# OperantFEDv8.net
KiCad netlist of a schematic drawn in EAGLE
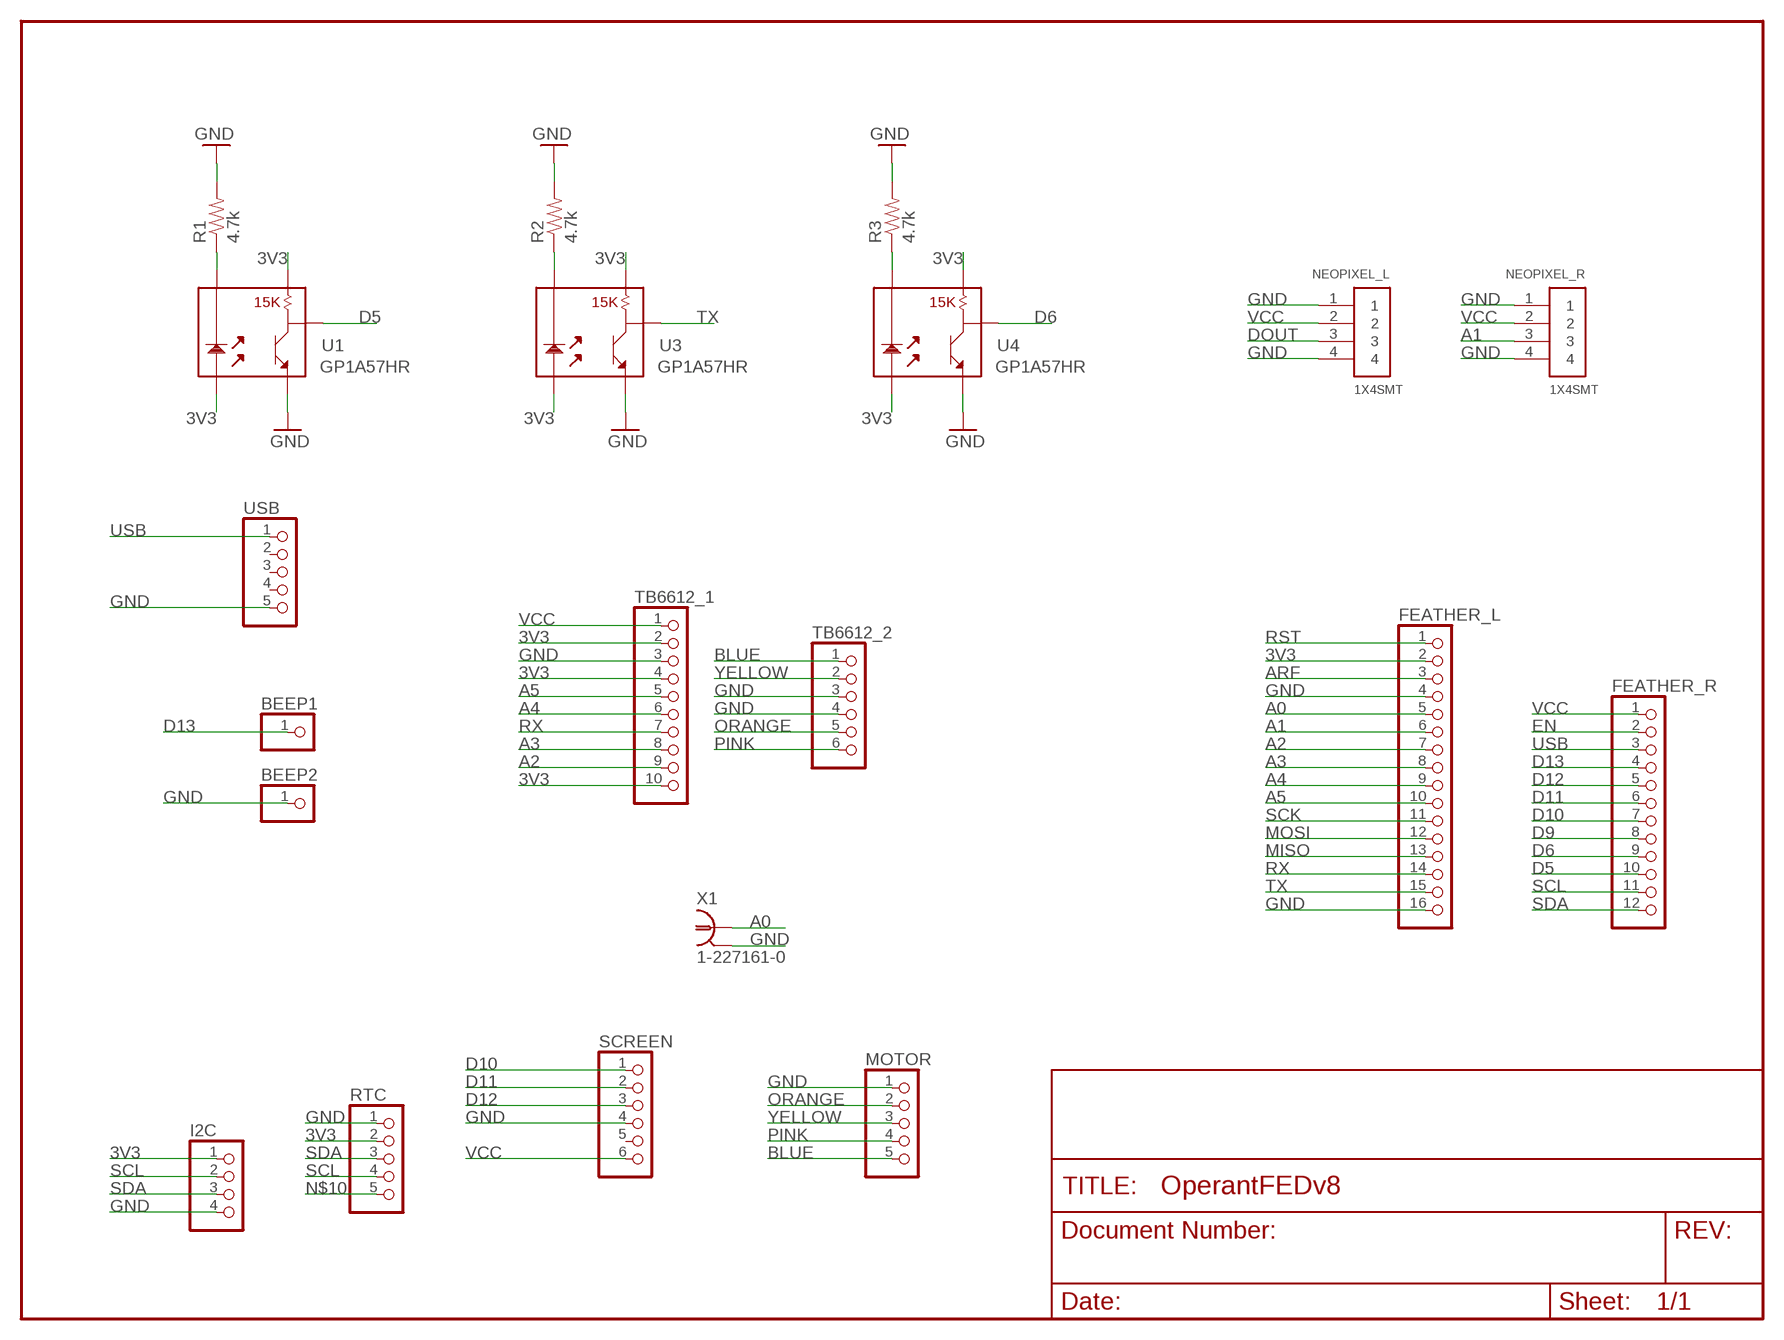
[diagram p0: schematic, sheet 1]

(export (version "E")
  (design (tool "Eeschema 10.0.6"))
  (components
    (comp (ref "BEEP1")
      (value "PINHD-1X1")
      (footprint "eagle-import:1X01")
      (libsource (lib "eagle-import") (part "PINHD-1X1"))
    )
    (comp (ref "BEEP2")
      (value "PINHD-1X1")
      (footprint "eagle-import:1X01")
      (libsource (lib "eagle-import") (part "PINHD-1X1"))
    )
    (comp (ref "FEATHER_L")
      (value "PINHD-1X16")
      (footprint "eagle-import:1X16")
      (libsource (lib "eagle-import") (part "PINHD-1X16"))
    )
    (comp (ref "FEATHER_R")
      (value "PINHD-1X12")
      (footprint "eagle-import:1X12")
      (libsource (lib "eagle-import") (part "PINHD-1X12"))
    )
    (comp (ref "I2C")
      (value "PINHD-1X4")
      (footprint "eagle-import:1X04")
      (libsource (lib "eagle-import") (part "PINHD-1X4"))
    )
    (comp (ref "MOTOR")
      (value "PINHD-1X5")
      (footprint "eagle-import:1X05")
      (libsource (lib "eagle-import") (part "PINHD-1X5"))
    )
    (comp (ref "NEOPIXEL_L")
      (value "1X4SMT")
      (footprint "eagle-import:1X4-SMT")
      (libsource (lib "eagle-import") (part "1X4SMT"))
    )
    (comp (ref "NEOPIXEL_R")
      (value "1X4SMT")
      (footprint "eagle-import:1X4-SMT")
      (libsource (lib "eagle-import") (part "1X4SMT"))
    )
    (comp (ref "R1")
      (value "4.7k")
      (footprint "eagle-import:AXIAL-0.3")
      (libsource (lib "eagle-import") (part "RESISTORPTH1"))
    )
    (comp (ref "R2")
      (value "4.7k")
      (footprint "eagle-import:AXIAL-0.3")
      (libsource (lib "eagle-import") (part "RESISTORPTH1"))
    )
    (comp (ref "R3")
      (value "4.7k")
      (footprint "eagle-import:AXIAL-0.3")
      (libsource (lib "eagle-import") (part "RESISTORPTH1"))
    )
    (comp (ref "RTC")
      (value "PINHD-1X5")
      (footprint "eagle-import:1X05")
      (libsource (lib "eagle-import") (part "PINHD-1X5"))
    )
    (comp (ref "SCREEN")
      (value "PINHD-1X6")
      (footprint "eagle-import:1X06")
      (libsource (lib "eagle-import") (part "PINHD-1X6"))
    )
    (comp (ref "TB6612_1")
      (value "PINHD-1X10")
      (footprint "eagle-import:1X10")
      (libsource (lib "eagle-import") (part "PINHD-1X10"))
    )
    (comp (ref "TB6612_2")
      (value "PINHD-1X6")
      (footprint "eagle-import:1X06")
      (libsource (lib "eagle-import") (part "PINHD-1X6"))
    )
    (comp (ref "U1")
      (value "GP1A57HR")
      (footprint "eagle-import:GP1A57HR")
      (libsource (lib "eagle-import") (part "GP1A57HR"))
    )
    (comp (ref "U3")
      (value "GP1A57HR")
      (footprint "eagle-import:GP1A57HR")
      (libsource (lib "eagle-import") (part "GP1A57HR"))
    )
    (comp (ref "U4")
      (value "GP1A57HR")
      (footprint "eagle-import:GP1A57HR")
      (libsource (lib "eagle-import") (part "GP1A57HR"))
    )
    (comp (ref "USB")
      (value "PINHD-1X5")
      (footprint "eagle-import:1X05")
      (libsource (lib "eagle-import") (part "PINHD-1X5"))
    )
    (comp (ref "X1")
      (value "1-227161-0")
      (footprint "eagle-import:AMP_227161")
      (fields (field (name "MF") "TYCO ELECTRONICS") (field (name "MPN") "1-227161"))
      (libsource (lib "eagle-import") (part "?2271611--0"))
    )
  )
  (nets
    (net (code "1") (name "/3V3") (class "Default")
      (node (ref "FEATHER_L") (pin "2") (pinfunction "2_2") (pintype "passive"))
      (node (ref "I2C") (pin "1") (pinfunction "1_1") (pintype "passive"))
      (node (ref "RTC") (pin "2") (pinfunction "2_2") (pintype "passive"))
      (node (ref "TB6612_1") (pin "10") (pinfunction "10_10") (pintype "passive"))
      (node (ref "TB6612_1") (pin "2") (pinfunction "2_2") (pintype "passive"))
      (node (ref "TB6612_1") (pin "4") (pinfunction "4_4") (pintype "passive"))
      (node (ref "U1") (pin "1") (pinfunction "1_1") (pintype "bidirectional"))
      (node (ref "U1") (pin "3") (pinfunction "3_3") (pintype "bidirectional"))
      (node (ref "U3") (pin "1") (pinfunction "1_1") (pintype "bidirectional"))
      (node (ref "U3") (pin "3") (pinfunction "3_3") (pintype "bidirectional"))
      (node (ref "U4") (pin "1") (pinfunction "1_1") (pintype "bidirectional"))
      (node (ref "U4") (pin "3") (pinfunction "3_3") (pintype "bidirectional"))
    )
    (net (code "2") (name "/A0") (class "Default")
      (node (ref "FEATHER_L") (pin "5") (pinfunction "5_5") (pintype "passive"))
      (node (ref "X1") (pin "1") (pinfunction "1_1") (pintype "passive"))
    )
    (net (code "3") (name "/A1") (class "Default")
      (node (ref "FEATHER_L") (pin "6") (pinfunction "6_6") (pintype "passive"))
      (node (ref "NEOPIXEL_R") (pin "3") (pinfunction "3_3") (pintype "bidirectional"))
    )
    (net (code "4") (name "/A2") (class "Default")
      (node (ref "FEATHER_L") (pin "7") (pinfunction "7_7") (pintype "passive"))
      (node (ref "TB6612_1") (pin "9") (pinfunction "9_9") (pintype "passive"))
    )
    (net (code "5") (name "/A3") (class "Default")
      (node (ref "FEATHER_L") (pin "8") (pinfunction "8_8") (pintype "passive"))
      (node (ref "TB6612_1") (pin "8") (pinfunction "8_8") (pintype "passive"))
    )
    (net (code "6") (name "/A4") (class "Default")
      (node (ref "FEATHER_L") (pin "9") (pinfunction "9_9") (pintype "passive"))
      (node (ref "TB6612_1") (pin "6") (pinfunction "6_6") (pintype "passive"))
    )
    (net (code "7") (name "/A5") (class "Default")
      (node (ref "FEATHER_L") (pin "10") (pinfunction "10_10") (pintype "passive"))
      (node (ref "TB6612_1") (pin "5") (pinfunction "5_5") (pintype "passive"))
    )
    (net (code "8") (name "/ARF") (class "Default")
      (node (ref "FEATHER_L") (pin "3") (pinfunction "3_3") (pintype "passive"))
    )
    (net (code "9") (name "/BLUE") (class "Default")
      (node (ref "MOTOR") (pin "5") (pinfunction "5_5") (pintype "passive"))
      (node (ref "TB6612_2") (pin "1") (pinfunction "1_1") (pintype "passive"))
    )
    (net (code "10") (name "/D5") (class "Default")
      (node (ref "FEATHER_R") (pin "10") (pinfunction "10_10") (pintype "passive"))
      (node (ref "U1") (pin "4") (pinfunction "4_4") (pintype "bidirectional"))
    )
    (net (code "11") (name "/D6") (class "Default")
      (node (ref "FEATHER_R") (pin "9") (pinfunction "9_9") (pintype "passive"))
      (node (ref "U4") (pin "4") (pinfunction "4_4") (pintype "bidirectional"))
    )
    (net (code "12") (name "/D9") (class "Default")
      (node (ref "FEATHER_R") (pin "8") (pinfunction "8_8") (pintype "passive"))
    )
    (net (code "13") (name "/D10") (class "Default")
      (node (ref "FEATHER_R") (pin "7") (pinfunction "7_7") (pintype "passive"))
      (node (ref "SCREEN") (pin "1") (pinfunction "1_1") (pintype "passive"))
    )
    (net (code "14") (name "/D11") (class "Default")
      (node (ref "FEATHER_R") (pin "6") (pinfunction "6_6") (pintype "passive"))
      (node (ref "SCREEN") (pin "2") (pinfunction "2_2") (pintype "passive"))
    )
    (net (code "15") (name "/D12") (class "Default")
      (node (ref "FEATHER_R") (pin "5") (pinfunction "5_5") (pintype "passive"))
      (node (ref "SCREEN") (pin "3") (pinfunction "3_3") (pintype "passive"))
    )
    (net (code "16") (name "/D13") (class "Default")
      (node (ref "BEEP1") (pin "1") (pinfunction "1_1") (pintype "passive"))
      (node (ref "FEATHER_R") (pin "4") (pinfunction "4_4") (pintype "passive"))
    )
    (net (code "17") (name "/DOUT") (class "Default")
      (node (ref "NEOPIXEL_L") (pin "3") (pinfunction "3_3") (pintype "bidirectional"))
    )
    (net (code "18") (name "/EN") (class "Default")
      (node (ref "FEATHER_R") (pin "2") (pinfunction "2_2") (pintype "passive"))
    )
    (net (code "19") (name "/MISO") (class "Default")
      (node (ref "FEATHER_L") (pin "13") (pinfunction "13_13") (pintype "passive"))
    )
    (net (code "20") (name "/MOSI") (class "Default")
      (node (ref "FEATHER_L") (pin "12") (pinfunction "12_12") (pintype "passive"))
    )
    (net (code "21") (name "/N$10") (class "Default")
      (node (ref "RTC") (pin "5") (pinfunction "5_5") (pintype "passive"))
    )
    (net (code "22") (name "/ORANGE") (class "Default")
      (node (ref "MOTOR") (pin "2") (pinfunction "2_2") (pintype "passive"))
      (node (ref "TB6612_2") (pin "5") (pinfunction "5_5") (pintype "passive"))
    )
    (net (code "23") (name "/PINK") (class "Default")
      (node (ref "MOTOR") (pin "4") (pinfunction "4_4") (pintype "passive"))
      (node (ref "TB6612_2") (pin "6") (pinfunction "6_6") (pintype "passive"))
    )
    (net (code "24") (name "/RST") (class "Default")
      (node (ref "FEATHER_L") (pin "1") (pinfunction "1_1") (pintype "passive"))
    )
    (net (code "25") (name "/RX") (class "Default")
      (node (ref "FEATHER_L") (pin "14") (pinfunction "14_14") (pintype "passive"))
      (node (ref "TB6612_1") (pin "7") (pinfunction "7_7") (pintype "passive"))
    )
    (net (code "26") (name "/SCK") (class "Default")
      (node (ref "FEATHER_L") (pin "11") (pinfunction "11_11") (pintype "passive"))
    )
    (net (code "27") (name "/SCL") (class "Default")
      (node (ref "FEATHER_R") (pin "11") (pinfunction "11_11") (pintype "passive"))
      (node (ref "I2C") (pin "2") (pinfunction "2_2") (pintype "passive"))
      (node (ref "RTC") (pin "4") (pinfunction "4_4") (pintype "passive"))
    )
    (net (code "28") (name "/SDA") (class "Default")
      (node (ref "FEATHER_R") (pin "12") (pinfunction "12_12") (pintype "passive"))
      (node (ref "I2C") (pin "3") (pinfunction "3_3") (pintype "passive"))
      (node (ref "RTC") (pin "3") (pinfunction "3_3") (pintype "passive"))
    )
    (net (code "29") (name "/TX") (class "Default")
      (node (ref "FEATHER_L") (pin "15") (pinfunction "15_15") (pintype "passive"))
      (node (ref "U3") (pin "4") (pinfunction "4_4") (pintype "bidirectional"))
    )
    (net (code "30") (name "/USB") (class "Default")
      (node (ref "FEATHER_R") (pin "3") (pinfunction "3_3") (pintype "passive"))
      (node (ref "USB") (pin "1") (pinfunction "1_1") (pintype "passive"))
    )
    (net (code "31") (name "/VCC") (class "Default")
      (node (ref "FEATHER_R") (pin "1") (pinfunction "1_1") (pintype "passive"))
      (node (ref "NEOPIXEL_L") (pin "2") (pinfunction "2_2") (pintype "bidirectional"))
      (node (ref "NEOPIXEL_R") (pin "2") (pinfunction "2_2") (pintype "bidirectional"))
      (node (ref "SCREEN") (pin "6") (pinfunction "6_6") (pintype "passive"))
      (node (ref "TB6612_1") (pin "1") (pinfunction "1_1") (pintype "passive"))
    )
    (net (code "32") (name "/YELLOW") (class "Default")
      (node (ref "MOTOR") (pin "3") (pinfunction "3_3") (pintype "passive"))
      (node (ref "TB6612_2") (pin "2") (pinfunction "2_2") (pintype "passive"))
    )
    (net (code "33") (name "GND") (class "Default")
      (node (ref "BEEP2") (pin "1") (pinfunction "1_1") (pintype "passive"))
      (node (ref "FEATHER_L") (pin "16") (pinfunction "16_16") (pintype "passive"))
      (node (ref "FEATHER_L") (pin "4") (pinfunction "4_4") (pintype "passive"))
      (node (ref "I2C") (pin "4") (pinfunction "4_4") (pintype "passive"))
      (node (ref "MOTOR") (pin "1") (pinfunction "1_1") (pintype "passive"))
      (node (ref "NEOPIXEL_L") (pin "1") (pinfunction "1_1") (pintype "bidirectional"))
      (node (ref "NEOPIXEL_L") (pin "4") (pinfunction "4_4") (pintype "bidirectional"))
      (node (ref "NEOPIXEL_R") (pin "1") (pinfunction "1_1") (pintype "bidirectional"))
      (node (ref "NEOPIXEL_R") (pin "4") (pinfunction "4_4") (pintype "bidirectional"))
      (node (ref "R1") (pin "P$2") (pinfunction "2_P$2") (pintype "passive"))
      (node (ref "R2") (pin "P$2") (pinfunction "2_P$2") (pintype "passive"))
      (node (ref "R3") (pin "P$2") (pinfunction "2_P$2") (pintype "passive"))
      (node (ref "RTC") (pin "1") (pinfunction "1_1") (pintype "passive"))
      (node (ref "SCREEN") (pin "4") (pinfunction "4_4") (pintype "passive"))
      (node (ref "TB6612_1") (pin "3") (pinfunction "3_3") (pintype "passive"))
      (node (ref "TB6612_2") (pin "3") (pinfunction "3_3") (pintype "passive"))
      (node (ref "TB6612_2") (pin "4") (pinfunction "4_4") (pintype "passive"))
      (node (ref "U1") (pin "5") (pinfunction "5_5") (pintype "bidirectional"))
      (node (ref "U3") (pin "5") (pinfunction "5_5") (pintype "bidirectional"))
      (node (ref "U4") (pin "5") (pinfunction "5_5") (pintype "bidirectional"))
      (node (ref "USB") (pin "5") (pinfunction "5_5") (pintype "passive"))
      (node (ref "X1") (pin "2") (pinfunction "2_2") (pintype "passive"))
    )
    (net (code "34") (name "Net-(R1-1)") (class "Default")
      (node (ref "R1") (pin "P$1") (pinfunction "1_P$1") (pintype "passive"))
      (node (ref "U1") (pin "2") (pinfunction "2_2") (pintype "bidirectional"))
    )
    (net (code "35") (name "Net-(R2-1)") (class "Default")
      (node (ref "R2") (pin "P$1") (pinfunction "1_P$1") (pintype "passive"))
      (node (ref "U3") (pin "2") (pinfunction "2_2") (pintype "bidirectional"))
    )
    (net (code "36") (name "Net-(R3-1)") (class "Default")
      (node (ref "R3") (pin "P$1") (pinfunction "1_P$1") (pintype "passive"))
      (node (ref "U4") (pin "2") (pinfunction "2_2") (pintype "bidirectional"))
    )
    (net (code "37") (name "unconnected-(SCREEN-Pad5)") (class "Default")
      (node (ref "SCREEN") (pin "5") (pinfunction "5_5") (pintype "passive"))
    )
    (net (code "38") (name "unconnected-(USB-Pad2)") (class "Default")
      (node (ref "USB") (pin "2") (pinfunction "2_2") (pintype "passive"))
    )
    (net (code "39") (name "unconnected-(USB-Pad3)") (class "Default")
      (node (ref "USB") (pin "3") (pinfunction "3_3") (pintype "passive"))
    )
    (net (code "40") (name "unconnected-(USB-Pad4)") (class "Default")
      (node (ref "USB") (pin "4") (pinfunction "4_4") (pintype "passive"))
    )
  )
)
